# NBT_JTAG_LOOP_CABLE.net
KiCad netlist of a schematic drawn in Altium Designer
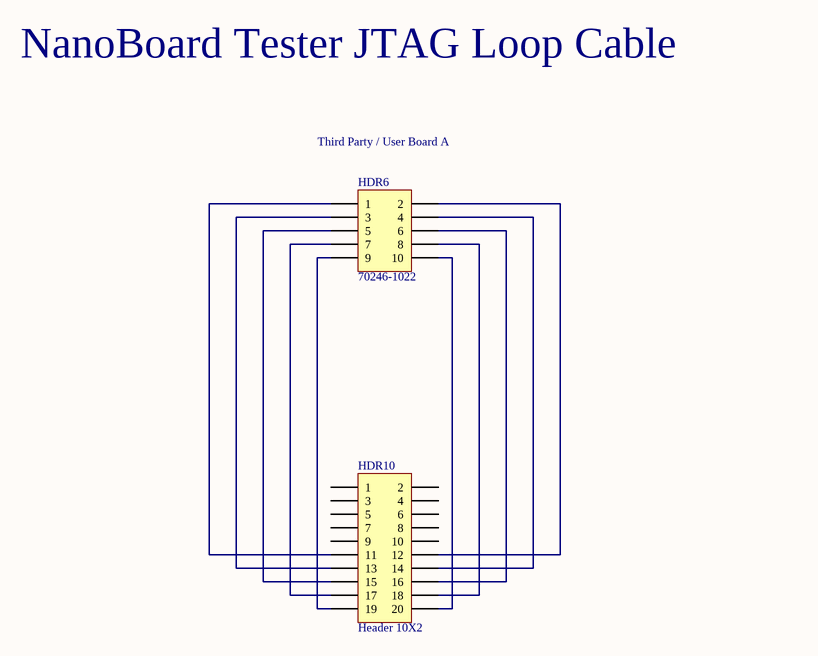
[diagram p0: NBT_JTAG_LOOP_CABLE.SCHDOC]

(export (version "E")
  (design (tool "Eeschema 10.0.6"))
  (components
    (comp (ref "HDR6")
      (value "70246-1022")
      (footprint "BOC1_4:HDR2X5_LP")
      (description "Header, 5-Pin, Dual row")
      (fields
        (field (name "MANUFACTURER") "Molex")
        (field (name "USAGE") "Third Party / User Board A")
        (field (name "PUBLISHER") "Altium Limited")
      )
      (libsource (lib "Miscellaneous Connectors") (part "Header 5X2"))
    )
    (comp (ref "HDR10")
      (value "Header 10X2")
      (footprint "HDR2X10")
      (description "Header, 10-Pin, Dual row")
      (fields (field (name "MANUFACTURER") "Generic Components") (field (name "PUBLISHER") "Altium Limited"))
      (libsource (lib "Miscellaneous Connectors") (part "Header 10X2"))
    )
  )
  (nets
    (net (code "1") (name "Net-(HDR10-Pad11)") (class "Default")
      (node (ref "HDR10") (pin "11") (pinfunction "11_11") (pintype "passive"))
      (node (ref "HDR6") (pin "1") (pinfunction "1_1") (pintype "passive"))
    )
    (net (code "2") (name "Net-(HDR10-Pad12)") (class "Default")
      (node (ref "HDR10") (pin "12") (pinfunction "12_12") (pintype "passive"))
      (node (ref "HDR6") (pin "2") (pinfunction "2_2") (pintype "passive"))
    )
    (net (code "3") (name "Net-(HDR10-Pad13)") (class "Default")
      (node (ref "HDR10") (pin "13") (pinfunction "13_13") (pintype "passive"))
      (node (ref "HDR6") (pin "3") (pinfunction "3_3") (pintype "passive"))
    )
    (net (code "4") (name "Net-(HDR10-Pad14)") (class "Default")
      (node (ref "HDR10") (pin "14") (pinfunction "14_14") (pintype "passive"))
      (node (ref "HDR6") (pin "4") (pinfunction "4_4") (pintype "passive"))
    )
    (net (code "5") (name "Net-(HDR10-Pad15)") (class "Default")
      (node (ref "HDR10") (pin "15") (pinfunction "15_15") (pintype "passive"))
      (node (ref "HDR6") (pin "5") (pinfunction "5_5") (pintype "passive"))
    )
    (net (code "6") (name "Net-(HDR10-Pad16)") (class "Default")
      (node (ref "HDR10") (pin "16") (pinfunction "16_16") (pintype "passive"))
      (node (ref "HDR6") (pin "6") (pinfunction "6_6") (pintype "passive"))
    )
    (net (code "7") (name "Net-(HDR10-Pad17)") (class "Default")
      (node (ref "HDR10") (pin "17") (pinfunction "17_17") (pintype "passive"))
      (node (ref "HDR6") (pin "7") (pinfunction "7_7") (pintype "passive"))
    )
    (net (code "8") (name "Net-(HDR10-Pad18)") (class "Default")
      (node (ref "HDR10") (pin "18") (pinfunction "18_18") (pintype "passive"))
      (node (ref "HDR6") (pin "8") (pinfunction "8_8") (pintype "passive"))
    )
    (net (code "9") (name "Net-(HDR10-Pad19)") (class "Default")
      (node (ref "HDR10") (pin "19") (pinfunction "19_19") (pintype "passive"))
      (node (ref "HDR6") (pin "9") (pinfunction "9_9") (pintype "passive"))
    )
    (net (code "10") (name "Net-(HDR10-Pad20)") (class "Default")
      (node (ref "HDR10") (pin "20") (pinfunction "20_20") (pintype "passive"))
      (node (ref "HDR6") (pin "10") (pinfunction "10_10") (pintype "passive"))
    )
    (net (code "11") (name "unconnected-(HDR10-Pad1)") (class "Default")
      (node (ref "HDR10") (pin "1") (pinfunction "1_1") (pintype "passive"))
    )
    (net (code "12") (name "unconnected-(HDR10-Pad2)") (class "Default")
      (node (ref "HDR10") (pin "2") (pinfunction "2_2") (pintype "passive"))
    )
    (net (code "13") (name "unconnected-(HDR10-Pad3)") (class "Default")
      (node (ref "HDR10") (pin "3") (pinfunction "3_3") (pintype "passive"))
    )
    (net (code "14") (name "unconnected-(HDR10-Pad4)") (class "Default")
      (node (ref "HDR10") (pin "4") (pinfunction "4_4") (pintype "passive"))
    )
    (net (code "15") (name "unconnected-(HDR10-Pad5)") (class "Default")
      (node (ref "HDR10") (pin "5") (pinfunction "5_5") (pintype "passive"))
    )
    (net (code "16") (name "unconnected-(HDR10-Pad6)") (class "Default")
      (node (ref "HDR10") (pin "6") (pinfunction "6_6") (pintype "passive"))
    )
    (net (code "17") (name "unconnected-(HDR10-Pad7)") (class "Default")
      (node (ref "HDR10") (pin "7") (pinfunction "7_7") (pintype "passive"))
    )
    (net (code "18") (name "unconnected-(HDR10-Pad8)") (class "Default")
      (node (ref "HDR10") (pin "8") (pinfunction "8_8") (pintype "passive"))
    )
    (net (code "19") (name "unconnected-(HDR10-Pad9)") (class "Default")
      (node (ref "HDR10") (pin "9") (pinfunction "9_9") (pintype "passive"))
    )
    (net (code "20") (name "unconnected-(HDR10-Pad10)") (class "Default")
      (node (ref "HDR10") (pin "10") (pinfunction "10_10") (pintype "passive"))
    )
  )
)
